# Interfaces.net
KiCad netlist of a schematic drawn in Altium Designer
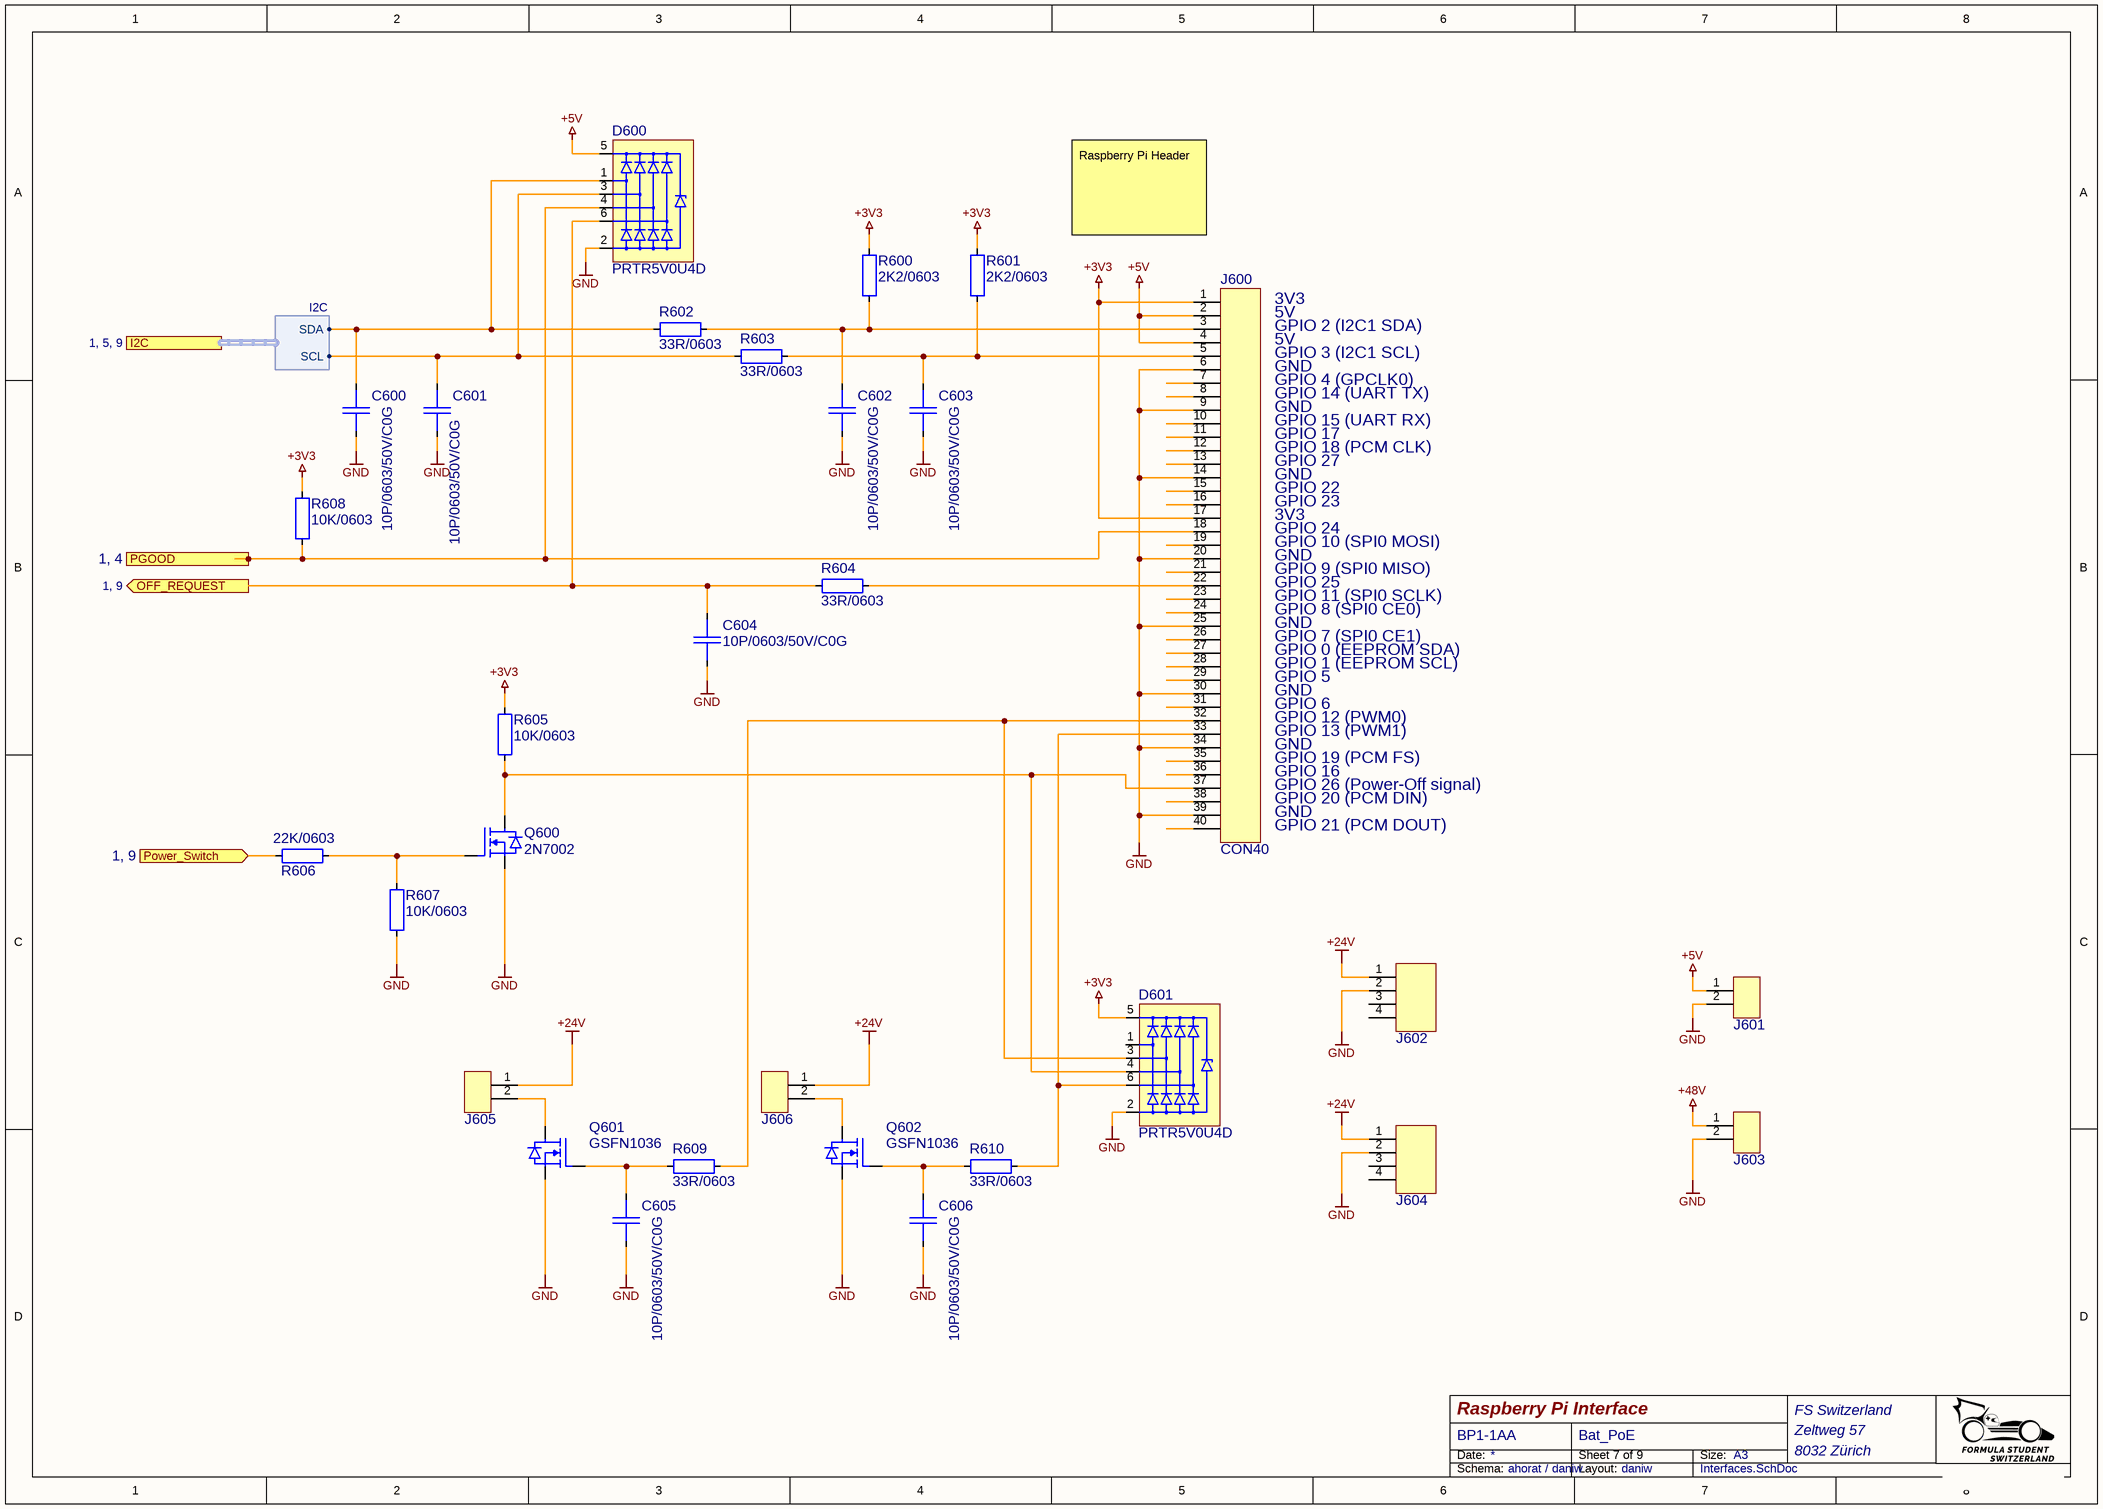
[diagram p0: Interfaces.SchDoc]

(export (version "E")
  (design (tool "Eeschema 10.0.6"))
  (components
    (comp (ref "C600")
      (value "10P/0603/50V/C0G")
      (footprint "CAP0603_C0G")
      (description "CAP SM 0603 10pF 50V C0G")
      (fields (field (name "MANUFACTURER") "GENERIC"))
      (libsource (lib "daniw_altium_lib") (part "C"))
    )
    (comp (ref "C601")
      (value "10P/0603/50V/C0G")
      (footprint "CAP0603_C0G")
      (description "CAP SM 0603 10pF 50V C0G")
      (fields (field (name "MANUFACTURER") "GENERIC"))
      (libsource (lib "daniw_altium_lib") (part "C"))
    )
    (comp (ref "C602")
      (value "10P/0603/50V/C0G")
      (footprint "CAP0603_C0G")
      (description "CAP SM 0603 10pF 50V C0G")
      (fields (field (name "MANUFACTURER") "GENERIC"))
      (libsource (lib "daniw_altium_lib") (part "C"))
    )
    (comp (ref "C603")
      (value "10P/0603/50V/C0G")
      (footprint "CAP0603_C0G")
      (description "CAP SM 0603 10pF 50V C0G")
      (fields (field (name "MANUFACTURER") "GENERIC"))
      (libsource (lib "daniw_altium_lib") (part "C"))
    )
    (comp (ref "C604")
      (value "10P/0603/50V/C0G")
      (footprint "CAP0603_C0G")
      (description "CAP SM 0603 10pF 50V C0G")
      (fields (field (name "MANUFACTURER") "GENERIC"))
      (libsource (lib "daniw_altium_lib") (part "C"))
    )
    (comp (ref "C605")
      (value "10P/0603/50V/C0G")
      (footprint "CAP0603_C0G")
      (description "CAP SM 0603 10pF 50V C0G")
      (fields (field (name "MANUFACTURER") "GENERIC"))
      (libsource (lib "daniw_altium_lib") (part "C"))
    )
    (comp (ref "C606")
      (value "10P/0603/50V/C0G")
      (footprint "CAP0603_C0G")
      (description "CAP SM 0603 10pF 50V C0G")
      (fields (field (name "MANUFACTURER") "GENERIC"))
      (libsource (lib "daniw_altium_lib") (part "C"))
    )
    (comp (ref "D600")
      (value "PRTR5V0U4D")
      (footprint "SOT2395P280X125-6-NW")
      (description "quadruple rail-to-rail ESD protection 5V")
      (fields (field (name "MANUFACTURER") "Nexperia"))
      (libsource (lib "daniw_altium_lib") (part "D_ESD_QUAD"))
    )
    (comp (ref "D601")
      (value "PRTR5V0U4D")
      (footprint "SOT2395P280X125-6-NW")
      (description "quadruple rail-to-rail ESD protection 5V")
      (fields (field (name "MANUFACTURER") "Nexperia"))
      (libsource (lib "daniw_altium_lib") (part "D_ESD_QUAD"))
    )
    (comp (ref "J600")
      (value "CON40")
      (footprint "HEAD_254_2X20_Tray")
      (description "Header 100 mil")
      (fields (field (name "PART NUMBER") "Header_2x20_Tray") (field (name "MANUFACTURER") "GENERIC"))
      (libsource (lib "daniw_altium_lib") (part "CON40"))
    )
    (comp (ref "J601")
      (value "5600200220")
      (footprint "5600200220")
      (description "DuraClik Wire-to-Board Header, Single Row, Vertical, 2 Circuits, Tin (Sn) Over Nickel, Natural")
      (fields (field (name "PART NUMBER") "DuraClick_1x2_VERT_SMD") (field (name "MANUFACTURER") "Molex"))
      (libsource (lib "daniw_altium_lib") (part "CON2"))
    )
    (comp (ref "J602")
      (value "430450412")
      (footprint "430450412")
      (fields (field (name "PART NUMBER") "Microfit_3.0_2x2_VERT_THT"))
      (libsource (lib "daniw_altium_lib") (part "CON4"))
    )
    (comp (ref "J603")
      (value "430450212")
      (footprint "430450212")
      (fields (field (name "PART NUMBER") "Microfit_3.0_1x2_VERT_THT"))
      (libsource (lib "daniw_altium_lib") (part "CON2"))
    )
    (comp (ref "J604")
      (value "430450412")
      (footprint "430450412")
      (fields (field (name "PART NUMBER") "Microfit_3.0_2x2_VERT_THT"))
      (libsource (lib "daniw_altium_lib") (part "CON4"))
    )
    (comp (ref "J605")
      (value "5600200220")
      (footprint "5600200220")
      (description "DuraClik Wire-to-Board Header, Single Row, Vertical, 2 Circuits, Tin (Sn) Over Nickel, Natural")
      (fields (field (name "PART NUMBER") "DuraClick_1x2_VERT_SMD") (field (name "MANUFACTURER") "Molex"))
      (libsource (lib "") (part "CON2_1"))
    )
    (comp (ref "J606")
      (value "5600200220")
      (footprint "5600200220")
      (description "DuraClik Wire-to-Board Header, Single Row, Vertical, 2 Circuits, Tin (Sn) Over Nickel, Natural")
      (fields (field (name "PART NUMBER") "DuraClick_1x2_VERT_SMD") (field (name "MANUFACTURER") "Molex"))
      (libsource (lib "") (part "CON2_1"))
    )
    (comp (ref "Q600")
      (value "2N7002")
      (footprint "SOT2395P280X125-3-SE")
      (description "60V 115mA 1.2Ω@10V,500mA 200mW 2.1V@250uA N Channel SOT-23 MOSFETs")
      (fields (field (name "MANUFACTURER") "GENERIC"))
      (libsource (lib "daniw_altium_lib") (part "MOSFET N_SOT23"))
    )
    (comp (ref "Q601")
      (value "GSFN1036")
      (footprint "SON065P330X330X075-5-TH245X175")
      (description "N-Kanal 100 V 35 A (Tc) 52W (Tc) Oberflächenmontage 8-PPAK (3,1x3,05)")
      (fields (field (name "MANUFACTURER") "Good-Ark Semiconductor"))
      (libsource (lib "daniw_altium_lib") (part "MOSFET N"))
    )
    (comp (ref "Q602")
      (value "GSFN1036")
      (footprint "SON065P330X330X075-5-TH245X175")
      (description "N-Kanal 100 V 35 A (Tc) 52W (Tc) Oberflächenmontage 8-PPAK (3,1x3,05)")
      (fields (field (name "MANUFACTURER") "Good-Ark Semiconductor"))
      (libsource (lib "daniw_altium_lib") (part "MOSFET N"))
    )
    (comp (ref "R600")
      (value "2K2/0603")
      (footprint "R0603-0.40-WW")
      (description "RES SM 0603 2K2")
      (fields (field (name "MANUFACTURER") "GENERIC"))
      (libsource (lib "daniw_altium_lib") (part "R"))
    )
    (comp (ref "R601")
      (value "2K2/0603")
      (footprint "R0603-0.40-WW")
      (description "RES SM 0603 2K2")
      (fields (field (name "MANUFACTURER") "GENERIC"))
      (libsource (lib "daniw_altium_lib") (part "R"))
    )
    (comp (ref "R602")
      (value "33R/0603")
      (footprint "R0603-0.40-WW")
      (description "RES SM 0603 33R")
      (fields (field (name "MANUFACTURER") "GENERIC"))
      (libsource (lib "daniw_altium_lib") (part "R"))
    )
    (comp (ref "R603")
      (value "33R/0603")
      (footprint "R0603-0.40-WW")
      (description "RES SM 0603 33R")
      (fields (field (name "MANUFACTURER") "GENERIC"))
      (libsource (lib "daniw_altium_lib") (part "R"))
    )
    (comp (ref "R604")
      (value "33R/0603")
      (footprint "R0603-0.40-WW")
      (description "RES SM 0603 33R")
      (fields (field (name "MANUFACTURER") "GENERIC"))
      (libsource (lib "daniw_altium_lib") (part "R"))
    )
    (comp (ref "R605")
      (value "10K/0603")
      (footprint "R0603-0.40-WW")
      (description "RES SM 0603 10K")
      (fields (field (name "MANUFACTURER") "GENERIC"))
      (libsource (lib "daniw_altium_lib") (part "R"))
    )
    (comp (ref "R606")
      (value "22K/0603")
      (footprint "R0603-0.40-WW")
      (description "RES SM 0603 22K")
      (fields (field (name "MANUFACTURER") "GENERIC"))
      (libsource (lib "daniw_altium_lib") (part "R"))
    )
    (comp (ref "R607")
      (value "10K/0603")
      (footprint "R0603-0.40-WW")
      (description "RES SM 0603 10K")
      (fields (field (name "MANUFACTURER") "GENERIC"))
      (libsource (lib "daniw_altium_lib") (part "R"))
    )
    (comp (ref "R608")
      (value "10K/0603")
      (footprint "R0603-0.40-WW")
      (description "RES SM 0603 10K")
      (fields (field (name "MANUFACTURER") "GENERIC"))
      (libsource (lib "daniw_altium_lib") (part "R"))
    )
    (comp (ref "R609")
      (value "33R/0603")
      (footprint "R0603-0.40-WW")
      (description "RES SM 0603 33R")
      (fields (field (name "MANUFACTURER") "GENERIC"))
      (libsource (lib "daniw_altium_lib") (part "R"))
    )
    (comp (ref "R610")
      (value "33R/0603")
      (footprint "R0603-0.40-WW")
      (description "RES SM 0603 33R")
      (fields (field (name "MANUFACTURER") "GENERIC"))
      (libsource (lib "daniw_altium_lib") (part "R"))
    )
  )
  (nets
    (net (code "2") (name "+3V3") (class "Default")
      (node (ref "D601") (pin "5") (pinfunction "5_5") (pintype "passive"))
      (node (ref "J600") (pin "1") (pintype "passive"))
      (node (ref "J600") (pin "17") (pintype "passive"))
      (node (ref "R600") (pin "2") (pinfunction "2_2") (pintype "passive"))
      (node (ref "R601") (pin "2") (pinfunction "2_2") (pintype "passive"))
      (node (ref "R605") (pin "1") (pinfunction "1_1") (pintype "passive"))
      (node (ref "R608") (pin "1") (pinfunction "1_1") (pintype "passive"))
    )
    (net (code "3") (name "+5V") (class "Default")
      (node (ref "D600") (pin "5") (pinfunction "5_5") (pintype "passive"))
      (node (ref "J600") (pin "2") (pintype "passive"))
      (node (ref "J600") (pin "4") (pintype "passive"))
      (node (ref "J601") (pin "1") (pintype "passive"))
    )
    (net (code "4") (name "+24V") (class "Default")
      (node (ref "J602") (pin "1") (pintype "passive"))
      (node (ref "J604") (pin "1") (pintype "passive"))
      (node (ref "J605") (pin "1") (pintype "passive"))
      (node (ref "J606") (pin "1") (pintype "passive"))
    )
    (net (code "5") (name "+48V") (class "Default") (node (ref "J603") (pin "1") (pintype "passive")))
    (net (code "6") (name "/OFF_REQUEST") (class "Default")
      (node (ref "C604") (pin "1") (pinfunction "1_1") (pintype "passive"))
      (node (ref "D600") (pin "6") (pinfunction "6_6") (pintype "passive"))
      (node (ref "R604") (pin "1") (pinfunction "1_1") (pintype "passive"))
    )
    (net (code "7") (name "/PGOOD") (class "Default")
      (node (ref "D600") (pin "4") (pinfunction "4_4") (pintype "passive"))
      (node (ref "J600") (pin "18") (pintype "passive"))
      (node (ref "R608") (pin "2") (pinfunction "2_2") (pintype "passive"))
    )
    (net (code "8") (name "/Power_Switch") (class "Default")
      (node (ref "R606") (pin "1") (pinfunction "1_1") (pintype "passive"))
    )
    (net (code "10") (name "GND") (class "Default")
      (node (ref "C600") (pin "2") (pinfunction "2_2") (pintype "passive"))
      (node (ref "C601") (pin "2") (pinfunction "2_2") (pintype "passive"))
      (node (ref "C602") (pin "2") (pinfunction "2_2") (pintype "passive"))
      (node (ref "C603") (pin "2") (pinfunction "2_2") (pintype "passive"))
      (node (ref "C604") (pin "2") (pinfunction "2_2") (pintype "passive"))
      (node (ref "C605") (pin "2") (pinfunction "2_2") (pintype "passive"))
      (node (ref "C606") (pin "2") (pinfunction "2_2") (pintype "passive"))
      (node (ref "D600") (pin "2") (pinfunction "2_2") (pintype "passive"))
      (node (ref "D601") (pin "2") (pinfunction "2_2") (pintype "passive"))
      (node (ref "J600") (pin "14") (pintype "passive"))
      (node (ref "J600") (pin "20") (pintype "passive"))
      (node (ref "J600") (pin "25") (pintype "passive"))
      (node (ref "J600") (pin "30") (pintype "passive"))
      (node (ref "J600") (pin "34") (pintype "passive"))
      (node (ref "J600") (pin "39") (pintype "passive"))
      (node (ref "J600") (pin "6") (pintype "passive"))
      (node (ref "J600") (pin "9") (pintype "passive"))
      (node (ref "J601") (pin "2") (pintype "passive"))
      (node (ref "J602") (pin "2") (pintype "passive"))
      (node (ref "J603") (pin "2") (pintype "passive"))
      (node (ref "J604") (pin "2") (pintype "passive"))
      (node (ref "Q600") (pin "2") (pinfunction "SOURCE_2") (pintype "passive"))
      (node (ref "Q601") (pin "S") (pinfunction "SOURCE_S") (pintype "passive"))
      (node (ref "Q602") (pin "S") (pinfunction "SOURCE_S") (pintype "passive"))
      (node (ref "R607") (pin "2") (pinfunction "2_2") (pintype "passive"))
    )
    (net (code "11") (name "Net-(C600-Pad1)") (class "Default")
      (node (ref "C600") (pin "1") (pinfunction "1_1") (pintype "passive"))
      (node (ref "D600") (pin "1") (pinfunction "1_1") (pintype "passive"))
      (node (ref "R602") (pin "1") (pinfunction "1_1") (pintype "passive"))
    )
    (net (code "12") (name "Net-(C601-Pad1)") (class "Default")
      (node (ref "C601") (pin "1") (pinfunction "1_1") (pintype "passive"))
      (node (ref "D600") (pin "3") (pinfunction "3_3") (pintype "passive"))
      (node (ref "R603") (pin "1") (pinfunction "1_1") (pintype "passive"))
    )
    (net (code "13") (name "Net-(C602-Pad1)") (class "Default")
      (node (ref "C602") (pin "1") (pinfunction "1_1") (pintype "passive"))
      (node (ref "J600") (pin "3") (pintype "passive"))
      (node (ref "R600") (pin "1") (pinfunction "1_1") (pintype "passive"))
      (node (ref "R602") (pin "2") (pinfunction "2_2") (pintype "passive"))
    )
    (net (code "14") (name "Net-(C603-Pad1)") (class "Default")
      (node (ref "C603") (pin "1") (pinfunction "1_1") (pintype "passive"))
      (node (ref "J600") (pin "5") (pintype "passive"))
      (node (ref "R601") (pin "1") (pinfunction "1_1") (pintype "passive"))
      (node (ref "R603") (pin "2") (pinfunction "2_2") (pintype "passive"))
    )
    (net (code "15") (name "Net-(D601-Pad3)") (class "Default")
      (node (ref "D601") (pin "3") (pinfunction "3_3") (pintype "passive"))
      (node (ref "J600") (pin "32") (pintype "passive"))
      (node (ref "R609") (pin "2") (pinfunction "2_2") (pintype "passive"))
    )
    (net (code "16") (name "Net-(D601-Pad6)") (class "Default")
      (node (ref "D601") (pin "6") (pinfunction "6_6") (pintype "passive"))
      (node (ref "J600") (pin "33") (pintype "passive"))
      (node (ref "R610") (pin "2") (pinfunction "2_2") (pintype "passive"))
    )
    (net (code "17") (name "Net-(J600-Pad22)") (class "Default")
      (node (ref "J600") (pin "22") (pintype "passive"))
      (node (ref "R604") (pin "2") (pinfunction "2_2") (pintype "passive"))
    )
    (net (code "18") (name "Net-(Q600-DRAIN)") (class "Default")
      (node (ref "D601") (pin "4") (pinfunction "4_4") (pintype "passive"))
      (node (ref "J600") (pin "37") (pintype "passive"))
      (node (ref "Q600") (pin "3") (pinfunction "DRAIN_3") (pintype "passive"))
      (node (ref "R605") (pin "2") (pinfunction "2_2") (pintype "passive"))
    )
    (net (code "19") (name "Net-(Q600-GATE)") (class "Default")
      (node (ref "Q600") (pin "1") (pinfunction "GATE_1") (pintype "passive"))
      (node (ref "R606") (pin "2") (pinfunction "2_2") (pintype "passive"))
      (node (ref "R607") (pin "1") (pinfunction "1_1") (pintype "passive"))
    )
    (net (code "20") (name "Net-(Q601-DRAIN)") (class "Default")
      (node (ref "J605") (pin "2") (pintype "passive"))
      (node (ref "Q601") (pin "D") (pinfunction "DRAIN_D") (pintype "passive"))
    )
    (net (code "21") (name "Net-(Q601-GATE)") (class "Default")
      (node (ref "C605") (pin "1") (pinfunction "1_1") (pintype "passive"))
      (node (ref "Q601") (pin "G") (pinfunction "GATE_G") (pintype "passive"))
      (node (ref "R609") (pin "1") (pinfunction "1_1") (pintype "passive"))
    )
    (net (code "22") (name "Net-(Q602-DRAIN)") (class "Default")
      (node (ref "J606") (pin "2") (pintype "passive"))
      (node (ref "Q602") (pin "D") (pinfunction "DRAIN_D") (pintype "passive"))
    )
    (net (code "23") (name "Net-(Q602-GATE)") (class "Default")
      (node (ref "C606") (pin "1") (pinfunction "1_1") (pintype "passive"))
      (node (ref "Q602") (pin "G") (pinfunction "GATE_G") (pintype "passive"))
      (node (ref "R610") (pin "1") (pinfunction "1_1") (pintype "passive"))
    )
    (net (code "24") (name "unconnected-(D601-Pad1)") (class "Default")
      (node (ref "D601") (pin "1") (pinfunction "1_1") (pintype "passive"))
    )
    (net (code "25") (name "unconnected-(J600-Pad7)") (class "Default")
      (node (ref "J600") (pin "7") (pintype "passive"))
    )
    (net (code "26") (name "unconnected-(J600-Pad8)") (class "Default")
      (node (ref "J600") (pin "8") (pintype "passive"))
    )
    (net (code "27") (name "unconnected-(J600-Pad10)") (class "Default")
      (node (ref "J600") (pin "10") (pintype "passive"))
    )
    (net (code "28") (name "unconnected-(J600-Pad11)") (class "Default")
      (node (ref "J600") (pin "11") (pintype "passive"))
    )
    (net (code "29") (name "unconnected-(J600-Pad12)") (class "Default")
      (node (ref "J600") (pin "12") (pintype "passive"))
    )
    (net (code "30") (name "unconnected-(J600-Pad13)") (class "Default")
      (node (ref "J600") (pin "13") (pintype "passive"))
    )
    (net (code "31") (name "unconnected-(J600-Pad15)") (class "Default")
      (node (ref "J600") (pin "15") (pintype "passive"))
    )
    (net (code "32") (name "unconnected-(J600-Pad16)") (class "Default")
      (node (ref "J600") (pin "16") (pintype "passive"))
    )
    (net (code "33") (name "unconnected-(J600-Pad19)") (class "Default")
      (node (ref "J600") (pin "19") (pintype "passive"))
    )
    (net (code "34") (name "unconnected-(J600-Pad21)") (class "Default")
      (node (ref "J600") (pin "21") (pintype "passive"))
    )
    (net (code "35") (name "unconnected-(J600-Pad23)") (class "Default")
      (node (ref "J600") (pin "23") (pintype "passive"))
    )
    (net (code "36") (name "unconnected-(J600-Pad24)") (class "Default")
      (node (ref "J600") (pin "24") (pintype "passive"))
    )
    (net (code "37") (name "unconnected-(J600-Pad26)") (class "Default")
      (node (ref "J600") (pin "26") (pintype "passive"))
    )
    (net (code "38") (name "unconnected-(J600-Pad27)") (class "Default")
      (node (ref "J600") (pin "27") (pintype "passive"))
    )
    (net (code "39") (name "unconnected-(J600-Pad28)") (class "Default")
      (node (ref "J600") (pin "28") (pintype "passive"))
    )
    (net (code "40") (name "unconnected-(J600-Pad29)") (class "Default")
      (node (ref "J600") (pin "29") (pintype "passive"))
    )
    (net (code "41") (name "unconnected-(J600-Pad31)") (class "Default")
      (node (ref "J600") (pin "31") (pintype "passive"))
    )
    (net (code "42") (name "unconnected-(J600-Pad35)") (class "Default")
      (node (ref "J600") (pin "35") (pintype "passive"))
    )
    (net (code "43") (name "unconnected-(J600-Pad36)") (class "Default")
      (node (ref "J600") (pin "36") (pintype "passive"))
    )
    (net (code "44") (name "unconnected-(J600-Pad38)") (class "Default")
      (node (ref "J600") (pin "38") (pintype "passive"))
    )
    (net (code "45") (name "unconnected-(J600-Pad40)") (class "Default")
      (node (ref "J600") (pin "40") (pintype "passive"))
    )
    (net (code "46") (name "unconnected-(J602-Pad3)") (class "Default")
      (node (ref "J602") (pin "3") (pintype "passive"))
    )
    (net (code "47") (name "unconnected-(J602-Pad4)") (class "Default")
      (node (ref "J602") (pin "4") (pintype "passive"))
    )
    (net (code "48") (name "unconnected-(J604-Pad3)") (class "Default")
      (node (ref "J604") (pin "3") (pintype "passive"))
    )
    (net (code "49") (name "unconnected-(J604-Pad4)") (class "Default")
      (node (ref "J604") (pin "4") (pintype "passive"))
    )
  )
)
